# Processor_Interface.net
KiCad netlist of a schematic drawn in Altium Designer
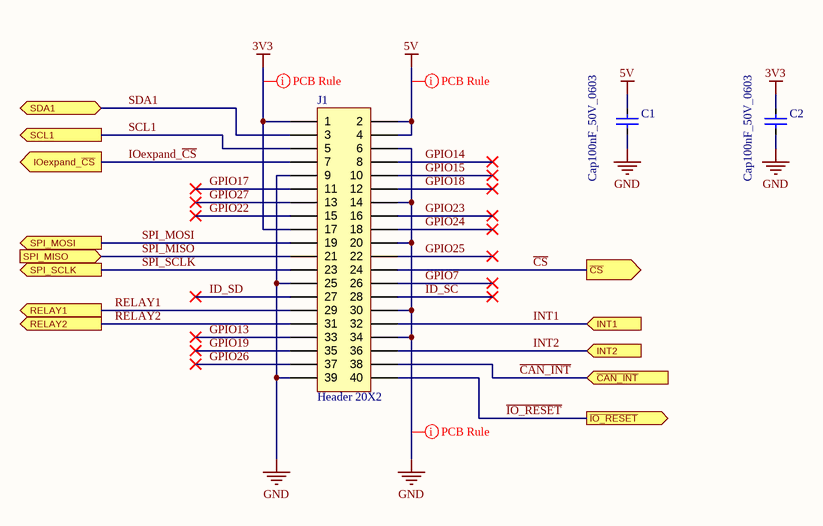
[diagram p0:  Processor_Interface.SchDoc]

(export (version "E")
  (design (tool "Eeschema 10.0.6"))
  (components
    (comp (ref "C1")
      (value "Cap100nF_50V_0603")
      (footprint "0603C_L")
      (libsource (lib " Advanced] Training Course - A365") (part "CAP General"))
    )
    (comp (ref "C2")
      (value "Cap100nF_50V_0603")
      (footprint "0603C_L")
      (libsource (lib " Advanced] Training Course - A365") (part "CAP General"))
    )
    (comp (ref "J1")
      (value "Header 20X2")
      (footprint "HDR2X20")
      (description "Header, 20-Pin, Dual row")
      (fields (field (name "PUBLISHER") "Altium Limited") (field (name "SOURCE") "WCT.SchLib"))
      (libsource (lib " Advanced] Training Course - A365") (part "Header 20X2"))
    )
  )
  (nets
    (net (code "1") (name "/CAN_INT") (class "Default")
      (node (ref "J1") (pin "38") (pinfunction "38_38") (pintype "passive"))
    )
    (net (code "2") (name "/GPIO7") (class "Default")
      (node (ref "J1") (pin "26") (pinfunction "26_26") (pintype "passive+no_connect"))
    )
    (net (code "3") (name "/GPIO13") (class "Default")
      (node (ref "J1") (pin "33") (pinfunction "33_33") (pintype "passive+no_connect"))
    )
    (net (code "4") (name "/GPIO14") (class "Default")
      (node (ref "J1") (pin "8") (pinfunction "8_8") (pintype "passive+no_connect"))
    )
    (net (code "5") (name "/GPIO15") (class "Default")
      (node (ref "J1") (pin "10") (pinfunction "10_10") (pintype "passive+no_connect"))
    )
    (net (code "6") (name "/GPIO17") (class "Default")
      (node (ref "J1") (pin "11") (pinfunction "11_11") (pintype "passive+no_connect"))
    )
    (net (code "7") (name "/GPIO18") (class "Default")
      (node (ref "J1") (pin "12") (pinfunction "12_12") (pintype "passive+no_connect"))
    )
    (net (code "8") (name "/GPIO19") (class "Default")
      (node (ref "J1") (pin "35") (pinfunction "35_35") (pintype "passive+no_connect"))
    )
    (net (code "9") (name "/GPIO22") (class "Default")
      (node (ref "J1") (pin "15") (pinfunction "15_15") (pintype "passive+no_connect"))
    )
    (net (code "10") (name "/GPIO23") (class "Default")
      (node (ref "J1") (pin "16") (pinfunction "16_16") (pintype "passive+no_connect"))
    )
    (net (code "11") (name "/GPIO24") (class "Default")
      (node (ref "J1") (pin "18") (pinfunction "18_18") (pintype "passive+no_connect"))
    )
    (net (code "12") (name "/GPIO25") (class "Default")
      (node (ref "J1") (pin "22") (pinfunction "22_22") (pintype "passive+no_connect"))
    )
    (net (code "13") (name "/GPIO26") (class "Default")
      (node (ref "J1") (pin "37") (pinfunction "37_37") (pintype "passive+no_connect"))
    )
    (net (code "14") (name "/GPIO27") (class "Default")
      (node (ref "J1") (pin "13") (pinfunction "13_13") (pintype "passive+no_connect"))
    )
    (net (code "15") (name "/ID_SC") (class "Default")
      (node (ref "J1") (pin "28") (pinfunction "28_28") (pintype "passive+no_connect"))
    )
    (net (code "16") (name "/ID_SD") (class "Default")
      (node (ref "J1") (pin "27") (pinfunction "27_27") (pintype "passive+no_connect"))
    )
    (net (code "17") (name "/INT1") (class "Default")
      (node (ref "J1") (pin "32") (pinfunction "32_32") (pintype "passive"))
    )
    (net (code "18") (name "/INT2") (class "Default")
      (node (ref "J1") (pin "36") (pinfunction "36_36") (pintype "passive"))
    )
    (net (code "19") (name "/IO_RESET") (class "Default")
      (node (ref "J1") (pin "40") (pinfunction "40_40") (pintype "passive"))
    )
    (net (code "20") (name "/IOexpand_~{CS}") (class "Default")
      (node (ref "J1") (pin "7") (pinfunction "7_7") (pintype "passive"))
    )
    (net (code "21") (name "/RELAY1") (class "Default")
      (node (ref "J1") (pin "29") (pinfunction "29_29") (pintype "passive"))
    )
    (net (code "22") (name "/RELAY2") (class "Default")
      (node (ref "J1") (pin "31") (pinfunction "31_31") (pintype "passive"))
    )
    (net (code "23") (name "/SCL1") (class "Default")
      (node (ref "J1") (pin "5") (pinfunction "5_5") (pintype "passive"))
    )
    (net (code "24") (name "/SDA1") (class "Default")
      (node (ref "J1") (pin "3") (pinfunction "3_3") (pintype "passive"))
    )
    (net (code "25") (name "/SPI_MISO") (class "Default")
      (node (ref "J1") (pin "21") (pinfunction "21_21") (pintype "passive"))
    )
    (net (code "26") (name "/SPI_MOSI") (class "Default")
      (node (ref "J1") (pin "19") (pinfunction "19_19") (pintype "passive"))
    )
    (net (code "27") (name "/SPI_SCLK") (class "Default")
      (node (ref "J1") (pin "23") (pinfunction "23_23") (pintype "passive"))
    )
    (net (code "28") (name "/~{CS}") (class "Default")
      (node (ref "J1") (pin "24") (pinfunction "24_24") (pintype "passive"))
    )
    (net (code "29") (name "3V3") (class "Default")
      (node (ref "C2") (pin "2") (pinfunction "2_2") (pintype "passive"))
      (node (ref "J1") (pin "1") (pinfunction "1_1") (pintype "passive"))
      (node (ref "J1") (pin "17") (pinfunction "17_17") (pintype "passive"))
    )
    (net (code "30") (name "5V") (class "Default")
      (node (ref "C1") (pin "2") (pinfunction "2_2") (pintype "passive"))
      (node (ref "J1") (pin "2") (pinfunction "2_2") (pintype "passive"))
      (node (ref "J1") (pin "4") (pinfunction "4_4") (pintype "passive"))
    )
    (net (code "31") (name "GND") (class "Default")
      (node (ref "C1") (pin "1") (pinfunction "1_1") (pintype "passive"))
      (node (ref "C2") (pin "1") (pinfunction "1_1") (pintype "passive"))
      (node (ref "J1") (pin "14") (pinfunction "14_14") (pintype "passive"))
      (node (ref "J1") (pin "20") (pinfunction "20_20") (pintype "passive"))
      (node (ref "J1") (pin "25") (pinfunction "25_25") (pintype "passive"))
      (node (ref "J1") (pin "30") (pinfunction "30_30") (pintype "passive"))
      (node (ref "J1") (pin "34") (pinfunction "34_34") (pintype "passive"))
      (node (ref "J1") (pin "39") (pinfunction "39_39") (pintype "passive"))
      (node (ref "J1") (pin "6") (pinfunction "6_6") (pintype "passive"))
      (node (ref "J1") (pin "9") (pinfunction "9_9") (pintype "passive"))
    )
  )
)
